# Slot_1b.net
KiCad netlist of a schematic drawn in Altium Designer
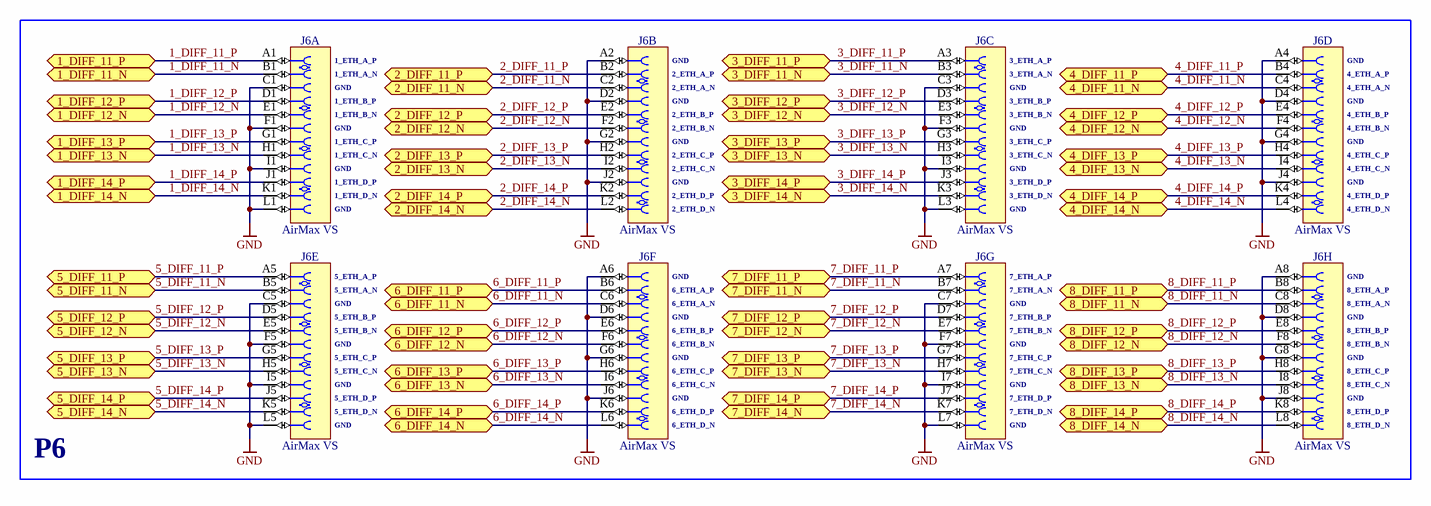
[diagram p0: Slot_1b.SchDoc]

(export (version "E")
  (design (tool "Eeschema 10.0.6"))
  (components
    (comp (ref "J6")
      (value "AirMax VS")
      (footprint "AMPHENOL_10052842-101LF")
      (description "96 Contacts Receptacle, 8 Columns, 4 Pairs per Column")
      (fields
        (field (name "PART NUMBER") "AMPHENOL_10052842-101LF")
        (field (name "MANUFACTURER") "AMPHENOL")
        (field (name "AUTHOR") "CERN DEM MR")
      )
      (libsource (lib "Connectors") (part "AMPHENOL_10052842-101LF"))
    )
  )
  (nets
    (net (code "1") (name "/1_DIFF_11_N") (class "Default")
      (node (ref "J6") (pin "B1") (pinfunction "B1_B1") (pintype "bidirectional"))
    )
    (net (code "2") (name "/1_DIFF_11_P") (class "Default")
      (node (ref "J6") (pin "A1") (pinfunction "A1_A1") (pintype "bidirectional"))
    )
    (net (code "3") (name "/1_DIFF_12_N") (class "Default")
      (node (ref "J6") (pin "E1") (pinfunction "E1_E1") (pintype "bidirectional"))
    )
    (net (code "4") (name "/1_DIFF_12_P") (class "Default")
      (node (ref "J6") (pin "D1") (pinfunction "D1_D1") (pintype "bidirectional"))
    )
    (net (code "5") (name "/1_DIFF_13_N") (class "Default")
      (node (ref "J6") (pin "H1") (pinfunction "H1_H1") (pintype "bidirectional"))
    )
    (net (code "6") (name "/1_DIFF_13_P") (class "Default")
      (node (ref "J6") (pin "G1") (pinfunction "G1_G1") (pintype "bidirectional"))
    )
    (net (code "7") (name "/1_DIFF_14_N") (class "Default")
      (node (ref "J6") (pin "K1") (pinfunction "K1_K1") (pintype "bidirectional"))
    )
    (net (code "8") (name "/1_DIFF_14_P") (class "Default")
      (node (ref "J6") (pin "J1") (pinfunction "J1_J1") (pintype "bidirectional"))
    )
    (net (code "9") (name "/2_DIFF_11_N") (class "Default")
      (node (ref "J6") (pin "C2") (pinfunction "C2_C2") (pintype "bidirectional"))
    )
    (net (code "10") (name "/2_DIFF_11_P") (class "Default")
      (node (ref "J6") (pin "B2") (pinfunction "B2_B2") (pintype "bidirectional"))
    )
    (net (code "11") (name "/2_DIFF_12_N") (class "Default")
      (node (ref "J6") (pin "F2") (pinfunction "F2_F2") (pintype "bidirectional"))
    )
    (net (code "12") (name "/2_DIFF_12_P") (class "Default")
      (node (ref "J6") (pin "E2") (pinfunction "E2_E2") (pintype "bidirectional"))
    )
    (net (code "13") (name "/2_DIFF_13_N") (class "Default")
      (node (ref "J6") (pin "I2") (pinfunction "I2_I2") (pintype "bidirectional"))
    )
    (net (code "14") (name "/2_DIFF_13_P") (class "Default")
      (node (ref "J6") (pin "H2") (pinfunction "H2_H2") (pintype "bidirectional"))
    )
    (net (code "15") (name "/2_DIFF_14_N") (class "Default")
      (node (ref "J6") (pin "L2") (pinfunction "L2_L2") (pintype "bidirectional"))
    )
    (net (code "16") (name "/2_DIFF_14_P") (class "Default")
      (node (ref "J6") (pin "K2") (pinfunction "K2_K2") (pintype "bidirectional"))
    )
    (net (code "17") (name "/3_DIFF_11_N") (class "Default")
      (node (ref "J6") (pin "B3") (pinfunction "B3_B3") (pintype "bidirectional"))
    )
    (net (code "18") (name "/3_DIFF_11_P") (class "Default")
      (node (ref "J6") (pin "A3") (pinfunction "A3_A3") (pintype "bidirectional"))
    )
    (net (code "19") (name "/3_DIFF_12_N") (class "Default")
      (node (ref "J6") (pin "E3") (pinfunction "E3_E3") (pintype "bidirectional"))
    )
    (net (code "20") (name "/3_DIFF_12_P") (class "Default")
      (node (ref "J6") (pin "D3") (pinfunction "D3_D3") (pintype "bidirectional"))
    )
    (net (code "21") (name "/3_DIFF_13_N") (class "Default")
      (node (ref "J6") (pin "H3") (pinfunction "H3_H3") (pintype "bidirectional"))
    )
    (net (code "22") (name "/3_DIFF_13_P") (class "Default")
      (node (ref "J6") (pin "G3") (pinfunction "G3_G3") (pintype "bidirectional"))
    )
    (net (code "23") (name "/3_DIFF_14_N") (class "Default")
      (node (ref "J6") (pin "K3") (pinfunction "K3_K3") (pintype "bidirectional"))
    )
    (net (code "24") (name "/3_DIFF_14_P") (class "Default")
      (node (ref "J6") (pin "J3") (pinfunction "J3_J3") (pintype "bidirectional"))
    )
    (net (code "25") (name "/4_DIFF_11_N") (class "Default")
      (node (ref "J6") (pin "C4") (pinfunction "C4_C4") (pintype "bidirectional"))
    )
    (net (code "26") (name "/4_DIFF_11_P") (class "Default")
      (node (ref "J6") (pin "B4") (pinfunction "B4_B4") (pintype "bidirectional"))
    )
    (net (code "27") (name "/4_DIFF_12_N") (class "Default")
      (node (ref "J6") (pin "F4") (pinfunction "F4_F4") (pintype "bidirectional"))
    )
    (net (code "28") (name "/4_DIFF_12_P") (class "Default")
      (node (ref "J6") (pin "E4") (pinfunction "E4_E4") (pintype "bidirectional"))
    )
    (net (code "29") (name "/4_DIFF_13_N") (class "Default")
      (node (ref "J6") (pin "I4") (pinfunction "I4_I4") (pintype "bidirectional"))
    )
    (net (code "30") (name "/4_DIFF_13_P") (class "Default")
      (node (ref "J6") (pin "H4") (pinfunction "H4_H4") (pintype "bidirectional"))
    )
    (net (code "31") (name "/4_DIFF_14_N") (class "Default")
      (node (ref "J6") (pin "L4") (pinfunction "L4_L4") (pintype "bidirectional"))
    )
    (net (code "32") (name "/4_DIFF_14_P") (class "Default")
      (node (ref "J6") (pin "K4") (pinfunction "K4_K4") (pintype "bidirectional"))
    )
    (net (code "33") (name "/5_DIFF_11_N") (class "Default")
      (node (ref "J6") (pin "B5") (pinfunction "B5_B5") (pintype "bidirectional"))
    )
    (net (code "34") (name "/5_DIFF_11_P") (class "Default")
      (node (ref "J6") (pin "A5") (pinfunction "A5_A5") (pintype "bidirectional"))
    )
    (net (code "35") (name "/5_DIFF_12_N") (class "Default")
      (node (ref "J6") (pin "E5") (pinfunction "E5_E5") (pintype "bidirectional"))
    )
    (net (code "36") (name "/5_DIFF_12_P") (class "Default")
      (node (ref "J6") (pin "D5") (pinfunction "D5_D5") (pintype "bidirectional"))
    )
    (net (code "37") (name "/5_DIFF_13_N") (class "Default")
      (node (ref "J6") (pin "H5") (pinfunction "H5_H5") (pintype "bidirectional"))
    )
    (net (code "38") (name "/5_DIFF_13_P") (class "Default")
      (node (ref "J6") (pin "G5") (pinfunction "G5_G5") (pintype "bidirectional"))
    )
    (net (code "39") (name "/5_DIFF_14_N") (class "Default")
      (node (ref "J6") (pin "K5") (pinfunction "K5_K5") (pintype "bidirectional"))
    )
    (net (code "40") (name "/5_DIFF_14_P") (class "Default")
      (node (ref "J6") (pin "J5") (pinfunction "J5_J5") (pintype "bidirectional"))
    )
    (net (code "41") (name "/6_DIFF_11_N") (class "Default")
      (node (ref "J6") (pin "C6") (pinfunction "C6_C6") (pintype "bidirectional"))
    )
    (net (code "42") (name "/6_DIFF_11_P") (class "Default")
      (node (ref "J6") (pin "B6") (pinfunction "B6_B6") (pintype "bidirectional"))
    )
    (net (code "43") (name "/6_DIFF_12_N") (class "Default")
      (node (ref "J6") (pin "F6") (pinfunction "F6_F6") (pintype "bidirectional"))
    )
    (net (code "44") (name "/6_DIFF_12_P") (class "Default")
      (node (ref "J6") (pin "E6") (pinfunction "E6_E6") (pintype "bidirectional"))
    )
    (net (code "45") (name "/6_DIFF_13_N") (class "Default")
      (node (ref "J6") (pin "I6") (pinfunction "I6_I6") (pintype "bidirectional"))
    )
    (net (code "46") (name "/6_DIFF_13_P") (class "Default")
      (node (ref "J6") (pin "H6") (pinfunction "H6_H6") (pintype "bidirectional"))
    )
    (net (code "47") (name "/6_DIFF_14_N") (class "Default")
      (node (ref "J6") (pin "L6") (pinfunction "L6_L6") (pintype "bidirectional"))
    )
    (net (code "48") (name "/6_DIFF_14_P") (class "Default")
      (node (ref "J6") (pin "K6") (pinfunction "K6_K6") (pintype "bidirectional"))
    )
    (net (code "49") (name "/7_DIFF_11_N") (class "Default")
      (node (ref "J6") (pin "B7") (pinfunction "B7_B7") (pintype "bidirectional"))
    )
    (net (code "50") (name "/7_DIFF_11_P") (class "Default")
      (node (ref "J6") (pin "A7") (pinfunction "A7_A7") (pintype "bidirectional"))
    )
    (net (code "51") (name "/7_DIFF_12_N") (class "Default")
      (node (ref "J6") (pin "E7") (pinfunction "E7_E7") (pintype "bidirectional"))
    )
    (net (code "52") (name "/7_DIFF_12_P") (class "Default")
      (node (ref "J6") (pin "D7") (pinfunction "D7_D7") (pintype "bidirectional"))
    )
    (net (code "53") (name "/7_DIFF_13_N") (class "Default")
      (node (ref "J6") (pin "H7") (pinfunction "H7_H7") (pintype "bidirectional"))
    )
    (net (code "54") (name "/7_DIFF_13_P") (class "Default")
      (node (ref "J6") (pin "G7") (pinfunction "G7_G7") (pintype "bidirectional"))
    )
    (net (code "55") (name "/7_DIFF_14_N") (class "Default")
      (node (ref "J6") (pin "K7") (pinfunction "K7_K7") (pintype "bidirectional"))
    )
    (net (code "56") (name "/7_DIFF_14_P") (class "Default")
      (node (ref "J6") (pin "J7") (pinfunction "J7_J7") (pintype "bidirectional"))
    )
    (net (code "57") (name "/8_DIFF_11_N") (class "Default")
      (node (ref "J6") (pin "C8") (pinfunction "C8_C8") (pintype "bidirectional"))
    )
    (net (code "58") (name "/8_DIFF_11_P") (class "Default")
      (node (ref "J6") (pin "B8") (pinfunction "B8_B8") (pintype "bidirectional"))
    )
    (net (code "59") (name "/8_DIFF_12_N") (class "Default")
      (node (ref "J6") (pin "F8") (pinfunction "F8_F8") (pintype "bidirectional"))
    )
    (net (code "60") (name "/8_DIFF_12_P") (class "Default")
      (node (ref "J6") (pin "E8") (pinfunction "E8_E8") (pintype "bidirectional"))
    )
    (net (code "61") (name "/8_DIFF_13_N") (class "Default")
      (node (ref "J6") (pin "I8") (pinfunction "I8_I8") (pintype "bidirectional"))
    )
    (net (code "62") (name "/8_DIFF_13_P") (class "Default")
      (node (ref "J6") (pin "H8") (pinfunction "H8_H8") (pintype "bidirectional"))
    )
    (net (code "63") (name "/8_DIFF_14_N") (class "Default")
      (node (ref "J6") (pin "L8") (pinfunction "L8_L8") (pintype "bidirectional"))
    )
    (net (code "64") (name "/8_DIFF_14_P") (class "Default")
      (node (ref "J6") (pin "K8") (pinfunction "K8_K8") (pintype "bidirectional"))
    )
    (net (code "65") (name "GND") (class "Default")
      (node (ref "J6") (pin "A2") (pinfunction "A2_A2") (pintype "bidirectional"))
      (node (ref "J6") (pin "A4") (pinfunction "A4_A4") (pintype "bidirectional"))
      (node (ref "J6") (pin "A6") (pinfunction "A6_A6") (pintype "bidirectional"))
      (node (ref "J6") (pin "A8") (pinfunction "A8_A8") (pintype "bidirectional"))
      (node (ref "J6") (pin "C1") (pinfunction "C1_C1") (pintype "bidirectional"))
      (node (ref "J6") (pin "C3") (pinfunction "C3_C3") (pintype "bidirectional"))
      (node (ref "J6") (pin "C5") (pinfunction "C5_C5") (pintype "bidirectional"))
      (node (ref "J6") (pin "C7") (pinfunction "C7_C7") (pintype "bidirectional"))
      (node (ref "J6") (pin "D2") (pinfunction "D2_D2") (pintype "bidirectional"))
      (node (ref "J6") (pin "D4") (pinfunction "D4_D4") (pintype "bidirectional"))
      (node (ref "J6") (pin "D6") (pinfunction "D6_D6") (pintype "bidirectional"))
      (node (ref "J6") (pin "D8") (pinfunction "D8_D8") (pintype "bidirectional"))
      (node (ref "J6") (pin "F1") (pinfunction "F1_F1") (pintype "bidirectional"))
      (node (ref "J6") (pin "F3") (pinfunction "F3_F3") (pintype "bidirectional"))
      (node (ref "J6") (pin "F5") (pinfunction "F5_F5") (pintype "bidirectional"))
      (node (ref "J6") (pin "F7") (pinfunction "F7_F7") (pintype "bidirectional"))
      (node (ref "J6") (pin "G2") (pinfunction "G2_G2") (pintype "bidirectional"))
      (node (ref "J6") (pin "G4") (pinfunction "G4_G4") (pintype "bidirectional"))
      (node (ref "J6") (pin "G6") (pinfunction "G6_G6") (pintype "bidirectional"))
      (node (ref "J6") (pin "G8") (pinfunction "G8_G8") (pintype "bidirectional"))
      (node (ref "J6") (pin "I1") (pinfunction "I1_I1") (pintype "bidirectional"))
      (node (ref "J6") (pin "I3") (pinfunction "I3_I3") (pintype "bidirectional"))
      (node (ref "J6") (pin "I5") (pinfunction "I5_I5") (pintype "bidirectional"))
      (node (ref "J6") (pin "I7") (pinfunction "I7_I7") (pintype "bidirectional"))
      (node (ref "J6") (pin "J2") (pinfunction "J2_J2") (pintype "bidirectional"))
      (node (ref "J6") (pin "J4") (pinfunction "J4_J4") (pintype "bidirectional"))
      (node (ref "J6") (pin "J6") (pinfunction "J6_J6") (pintype "bidirectional"))
      (node (ref "J6") (pin "J8") (pinfunction "J8_J8") (pintype "bidirectional"))
      (node (ref "J6") (pin "L1") (pinfunction "L1_L1") (pintype "bidirectional"))
      (node (ref "J6") (pin "L3") (pinfunction "L3_L3") (pintype "bidirectional"))
      (node (ref "J6") (pin "L5") (pinfunction "L5_L5") (pintype "bidirectional"))
      (node (ref "J6") (pin "L7") (pinfunction "L7_L7") (pintype "bidirectional"))
    )
  )
)
